# CAN-Bus-Interface.net
KiCad netlist of a schematic drawn in EAGLE
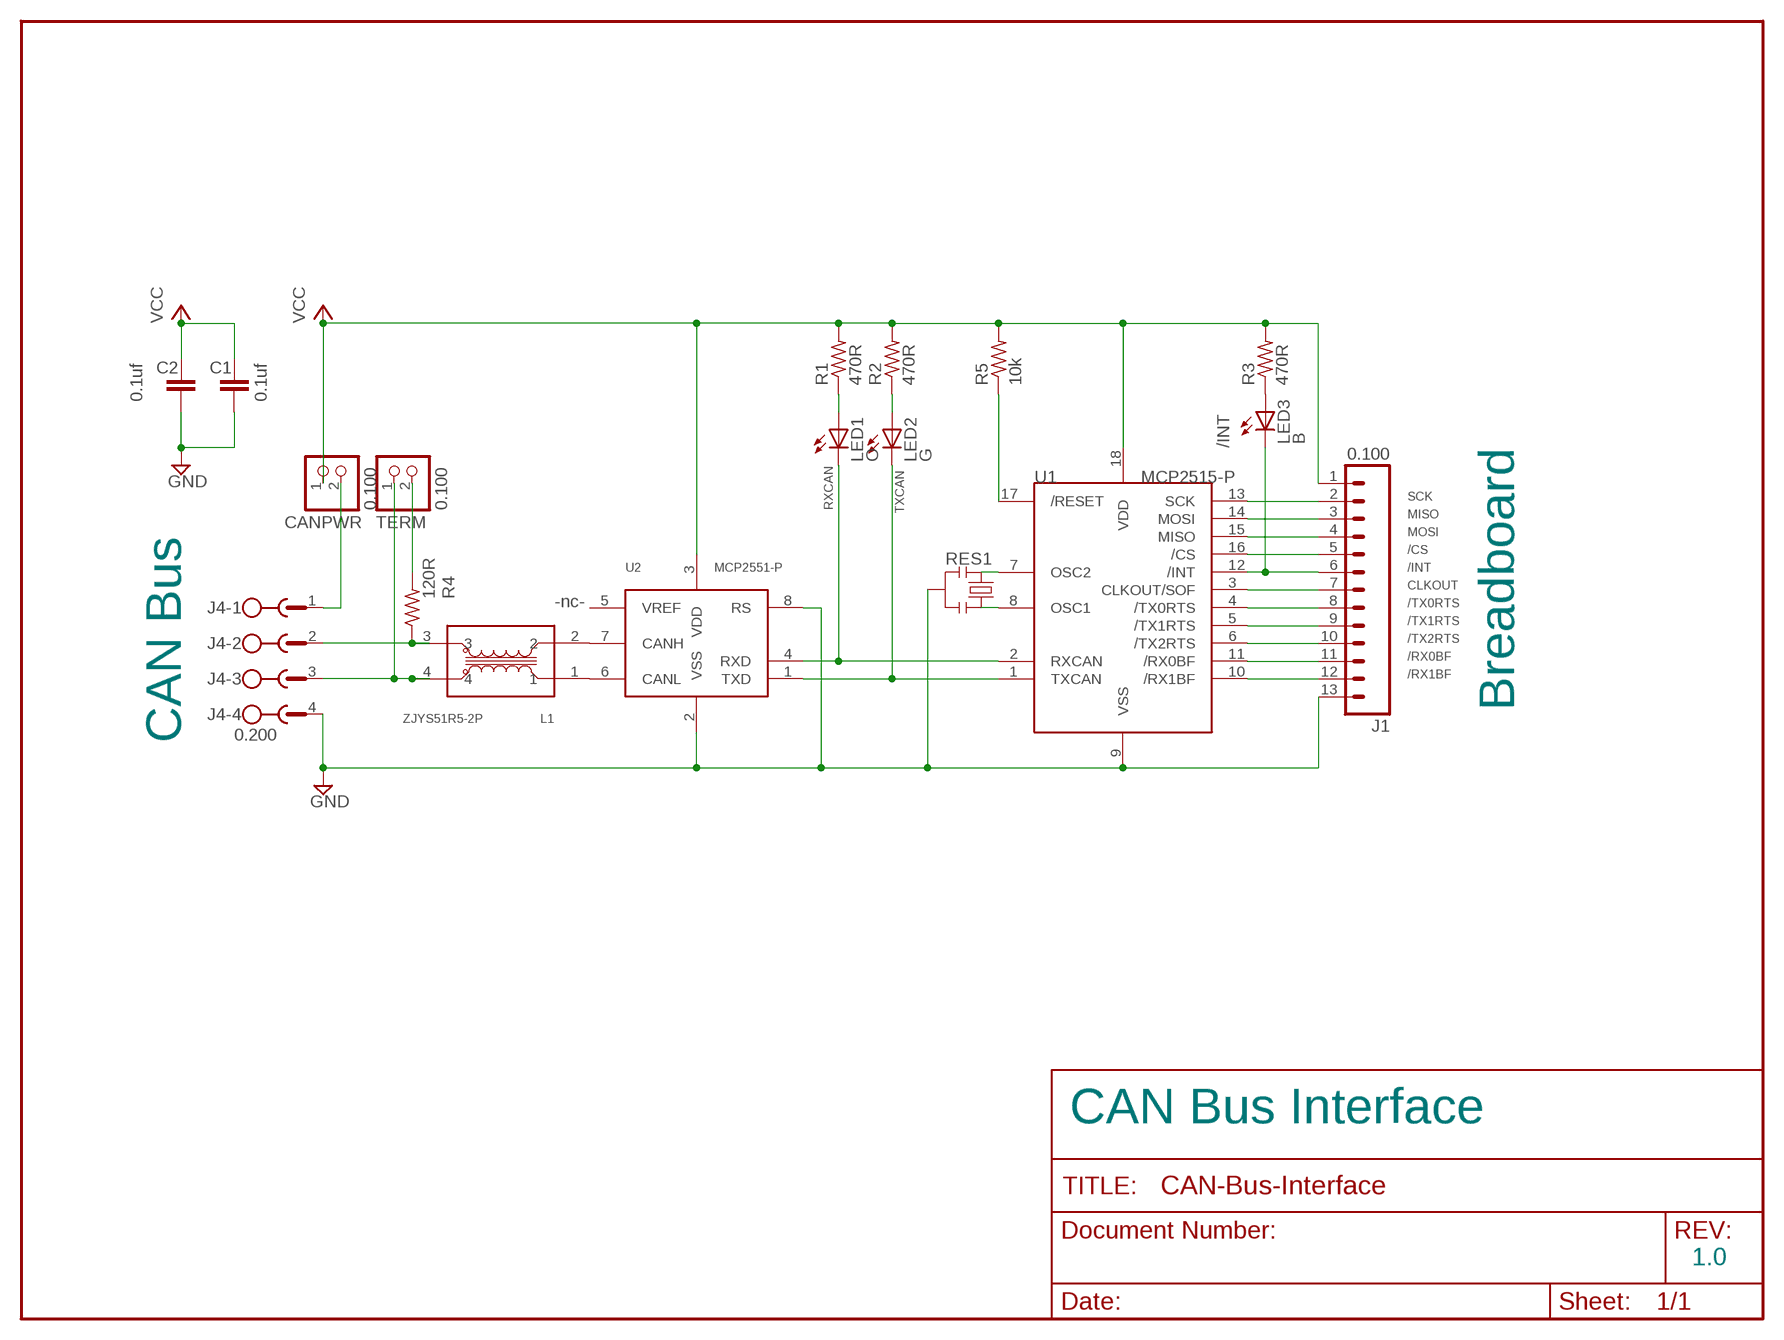
[diagram p0: schematic, sheet 1]

(export (version "E")
  (design (tool "Eeschema 10.0.6"))
  (components
    (comp (ref "C1")
      (value "0.1uf")
      (footprint "eagle-import:CAP-PTH-SMALL2")
      (libsource (lib "eagle-import") (part "CAPPTH2"))
    )
    (comp (ref "C2")
      (value "0.1uf")
      (footprint "eagle-import:CAP-PTH-SMALL2")
      (libsource (lib "eagle-import") (part "CAPPTH2"))
    )
    (comp (ref "CANPWR")
      (value "0.100")
      (footprint "eagle-import:1X02")
      (libsource (lib "eagle-import") (part "PINHD-1X2"))
    )
    (comp (ref "J1")
      (value "0.100")
      (footprint "eagle-import:1X13")
      (libsource (lib "eagle-import") (part "M13"))
    )
    (comp (ref "J4")
      (value "0.200")
      (footprint "eagle-import:MSTBV4")
      (libsource (lib "eagle-import") (part "MST4V"))
    )
    (comp (ref "L1")
      (value "ZJYS51R5-2P")
      (footprint "eagle-import:ZJYS")
      (libsource (lib "eagle-import") (part "ZJYS51R5-2P"))
    )
    (comp (ref "LED1")
      (value "O")
      (footprint "eagle-import:Q62902-B155")
      (libsource (lib "eagle-import") (part "LEDB155"))
    )
    (comp (ref "LED2")
      (value "G")
      (footprint "eagle-import:Q62902-B155")
      (libsource (lib "eagle-import") (part "LEDB155"))
    )
    (comp (ref "LED3")
      (value "B")
      (footprint "eagle-import:Q62902-B155")
      (libsource (lib "eagle-import") (part "LEDB155"))
    )
    (comp (ref "R1")
      (value "470R")
      (footprint "eagle-import:0204_5")
      (libsource (lib "eagle-import") (part "R-US_0204/5"))
    )
    (comp (ref "R2")
      (value "470R")
      (footprint "eagle-import:0204_5")
      (libsource (lib "eagle-import") (part "R-US_0204/5"))
    )
    (comp (ref "R3")
      (value "470R")
      (footprint "eagle-import:0204_5")
      (libsource (lib "eagle-import") (part "R-US_0204/5"))
    )
    (comp (ref "R4")
      (value "120R")
      (footprint "eagle-import:0204_5")
      (libsource (lib "eagle-import") (part "R-US_0204/5"))
    )
    (comp (ref "R5")
      (value "10k")
      (footprint "eagle-import:0204_5")
      (libsource (lib "eagle-import") (part "R-US_0204/5"))
    )
    (comp (ref "RES1")
      (value "RESONATORPTH")
      (footprint "eagle-import:RESONATOR-PTH")
      (libsource (lib "eagle-import") (part "RESONATORPTH"))
    )
    (comp (ref "TERM")
      (value "0.100")
      (footprint "eagle-import:1X02")
      (libsource (lib "eagle-import") (part "PINHD-1X2"))
    )
    (comp (ref "U1")
      (value "MCP2515-P")
      (footprint "eagle-import:DIL18")
      (libsource (lib "eagle-import") (part "MCP2515-P"))
    )
    (comp (ref "U2")
      (value "MCP2551-P")
      (footprint "eagle-import:DIL08")
      (libsource (lib "eagle-import") (part "MCP2551-P"))
    )
  )
  (nets
    (net (code "1") (name "/CLKOUT") (class "Default")
      (node (ref "J1") (pin "7") (pinfunction "7_7") (pintype "passive"))
      (node (ref "U1") (pin "3") (pinfunction "CLKOUT/SOF_3") (pintype "bidirectional"))
    )
    (net (code "2") (name "/MISO") (class "Default")
      (node (ref "J1") (pin "3") (pinfunction "3_3") (pintype "passive"))
      (node (ref "U1") (pin "14") (pinfunction "MOSI_14") (pintype "bidirectional"))
    )
    (net (code "3") (name "/MOSI") (class "Default")
      (node (ref "J1") (pin "4") (pinfunction "4_4") (pintype "passive"))
      (node (ref "U1") (pin "15") (pinfunction "MISO_15") (pintype "bidirectional"))
    )
    (net (code "4") (name "/RXCAN") (class "Default")
      (node (ref "LED1") (pin "A") (pinfunction "C_A") (pintype "passive"))
      (node (ref "U1") (pin "2") (pinfunction "RXCAN_2") (pintype "input"))
      (node (ref "U2") (pin "4") (pinfunction "RXD_4") (pintype "bidirectional"))
    )
    (net (code "5") (name "/SCK") (class "Default")
      (node (ref "J1") (pin "2") (pinfunction "2_2") (pintype "passive"))
      (node (ref "U1") (pin "13") (pinfunction "SCK_13") (pintype "bidirectional"))
    )
    (net (code "6") (name "/TXCAN") (class "Default")
      (node (ref "LED2") (pin "A") (pinfunction "C_A") (pintype "passive"))
      (node (ref "U1") (pin "1") (pinfunction "TXCAN_1") (pintype "output"))
      (node (ref "U2") (pin "1") (pinfunction "TXD_1") (pintype "bidirectional"))
    )
    (net (code "7") (name "/{slash}CS") (class "Default")
      (node (ref "J1") (pin "5") (pinfunction "5_5") (pintype "passive"))
      (node (ref "U1") (pin "16") (pinfunction "/CS_16") (pintype "bidirectional"))
    )
    (net (code "8") (name "/{slash}INT") (class "Default")
      (node (ref "J1") (pin "6") (pinfunction "6_6") (pintype "passive"))
      (node (ref "LED3") (pin "A") (pinfunction "C_A") (pintype "passive"))
      (node (ref "U1") (pin "12") (pinfunction "/INT_12") (pintype "output"))
    )
    (net (code "9") (name "/{slash}RX0BF") (class "Default")
      (node (ref "J1") (pin "11") (pinfunction "11_11") (pintype "passive"))
      (node (ref "U1") (pin "11") (pinfunction "/RX0BF_11") (pintype "bidirectional"))
    )
    (net (code "10") (name "/{slash}RX1BF") (class "Default")
      (node (ref "J1") (pin "12") (pinfunction "12_12") (pintype "passive"))
      (node (ref "U1") (pin "10") (pinfunction "/RX1BF_10") (pintype "bidirectional"))
    )
    (net (code "11") (name "/{slash}TX0RTS") (class "Default")
      (node (ref "J1") (pin "8") (pinfunction "8_8") (pintype "passive"))
      (node (ref "U1") (pin "4") (pinfunction "/TX0RTS_4") (pintype "bidirectional"))
    )
    (net (code "12") (name "/{slash}TX1RTS") (class "Default")
      (node (ref "J1") (pin "9") (pinfunction "9_9") (pintype "passive"))
      (node (ref "U1") (pin "5") (pinfunction "/TX1RTS_5") (pintype "bidirectional"))
    )
    (net (code "13") (name "/{slash}TX2RTS") (class "Default")
      (node (ref "J1") (pin "10") (pinfunction "10_10") (pintype "passive"))
      (node (ref "U1") (pin "6") (pinfunction "/TX2RTS_6") (pintype "bidirectional"))
    )
    (net (code "14") (name "GND") (class "Default")
      (node (ref "C1") (pin "2") (pinfunction "2_2") (pintype "passive"))
      (node (ref "C2") (pin "2") (pinfunction "2_2") (pintype "passive"))
      (node (ref "J1") (pin "13") (pinfunction "13_13") (pintype "passive"))
      (node (ref "J4") (pin "4") (pinfunction "1_4") (pintype "passive"))
      (node (ref "RES1") (pin "2") (pinfunction "2_2") (pintype "passive"))
      (node (ref "U1") (pin "9") (pinfunction "VSS_9") (pintype "power_in"))
      (node (ref "U2") (pin "2") (pinfunction "VSS_2") (pintype "power_in"))
      (node (ref "U2") (pin "8") (pinfunction "RS_8") (pintype "bidirectional"))
    )
    (net (code "15") (name "Net-(CANPWR-Pad2)") (class "Default")
      (node (ref "CANPWR") (pin "2") (pinfunction "2_2") (pintype "passive"))
      (node (ref "J4") (pin "1") (pinfunction "1_1") (pintype "passive"))
    )
    (net (code "16") (name "Net-(J4B-1)") (class "Default")
      (node (ref "J4") (pin "2") (pinfunction "1_2") (pintype "passive"))
      (node (ref "L1") (pin "3") (pinfunction "3_3") (pintype "bidirectional"))
      (node (ref "R4") (pin "1") (pinfunction "1_1") (pintype "passive"))
    )
    (net (code "17") (name "Net-(J4C-1)") (class "Default")
      (node (ref "J4") (pin "3") (pinfunction "1_3") (pintype "passive"))
      (node (ref "L1") (pin "4") (pinfunction "4_4") (pintype "bidirectional"))
      (node (ref "TERM") (pin "1") (pinfunction "1_1") (pintype "passive"))
    )
    (net (code "18") (name "Net-(LED1-A)") (class "Default")
      (node (ref "LED1") (pin "K") (pinfunction "A_K") (pintype "passive"))
      (node (ref "R1") (pin "1") (pinfunction "1_1") (pintype "passive"))
    )
    (net (code "19") (name "Net-(LED2-A)") (class "Default")
      (node (ref "LED2") (pin "K") (pinfunction "A_K") (pintype "passive"))
      (node (ref "R2") (pin "1") (pinfunction "1_1") (pintype "passive"))
    )
    (net (code "20") (name "Net-(LED3-A)") (class "Default")
      (node (ref "LED3") (pin "K") (pinfunction "A_K") (pintype "passive"))
      (node (ref "R3") (pin "1") (pinfunction "1_1") (pintype "passive"))
    )
    (net (code "21") (name "Net-(R4-Pad2)") (class "Default")
      (node (ref "R4") (pin "2") (pinfunction "2_2") (pintype "passive"))
      (node (ref "TERM") (pin "2") (pinfunction "2_2") (pintype "passive"))
    )
    (net (code "22") (name "Net-(U1-OSC1)") (class "Default")
      (node (ref "RES1") (pin "3") (pinfunction "3_3") (pintype "passive"))
      (node (ref "U1") (pin "8") (pinfunction "OSC1_8") (pintype "input"))
    )
    (net (code "23") (name "Net-(U1-OSC2)") (class "Default")
      (node (ref "RES1") (pin "1") (pinfunction "1_1") (pintype "passive"))
      (node (ref "U1") (pin "7") (pinfunction "OSC2_7") (pintype "input"))
    )
    (net (code "24") (name "Net-(U1-{slash}RESET)") (class "Default")
      (node (ref "R5") (pin "1") (pinfunction "1_1") (pintype "passive"))
      (node (ref "U1") (pin "17") (pinfunction "/RESET_17") (pintype "bidirectional"))
    )
    (net (code "25") (name "Net-(U2-CANH)") (class "Default")
      (node (ref "L1") (pin "2") (pinfunction "2_2") (pintype "bidirectional"))
      (node (ref "U2") (pin "7") (pinfunction "CANH_7") (pintype "bidirectional"))
    )
    (net (code "26") (name "Net-(U2-CANL)") (class "Default")
      (node (ref "L1") (pin "1") (pinfunction "1_1") (pintype "bidirectional"))
      (node (ref "U2") (pin "6") (pinfunction "CANL_6") (pintype "bidirectional"))
    )
    (net (code "27") (name "VCC") (class "Default")
      (node (ref "C1") (pin "1") (pinfunction "1_1") (pintype "passive"))
      (node (ref "C2") (pin "1") (pinfunction "1_1") (pintype "passive"))
      (node (ref "CANPWR") (pin "1") (pinfunction "1_1") (pintype "passive"))
      (node (ref "J1") (pin "1") (pinfunction "1_1") (pintype "passive"))
      (node (ref "R1") (pin "2") (pinfunction "2_2") (pintype "passive"))
      (node (ref "R2") (pin "2") (pinfunction "2_2") (pintype "passive"))
      (node (ref "R3") (pin "2") (pinfunction "2_2") (pintype "passive"))
      (node (ref "R5") (pin "2") (pinfunction "2_2") (pintype "passive"))
      (node (ref "U1") (pin "18") (pinfunction "VDD_18") (pintype "power_in"))
      (node (ref "U2") (pin "3") (pinfunction "VDD_3") (pintype "power_in"))
    )
    (net (code "28") (name "unconnected-(U2-VREF-Pad5)") (class "Default")
      (node (ref "U2") (pin "5") (pinfunction "VREF_5") (pintype "bidirectional"))
    )
  )
)
